# PSU.net
KiCad netlist of a schematic drawn in Altium Designer
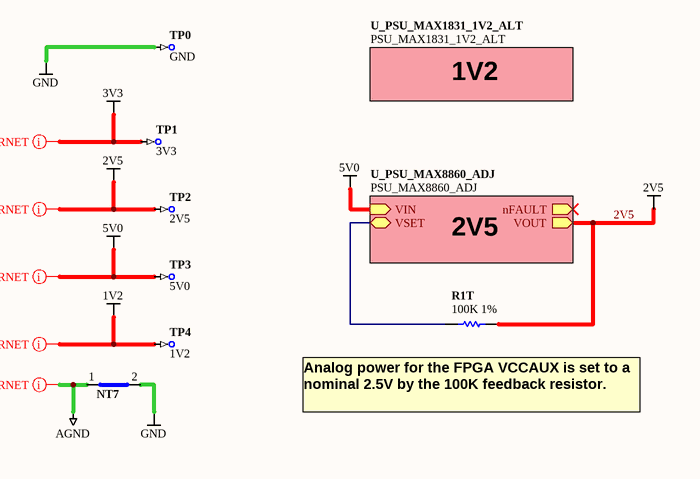
[diagram p0: PSU.SCHDOC]

(export (version "E")
  (design (tool "Eeschema 10.0.6"))
  (components
    (comp (ref "NT7")
      (value "Net Tie SMT2")
      (footprint "NETTIE-SMT2-8X8")
      (description "Net-Tie, Surface Mount, 2 x 0.4mm x 0.2mm SMT Pads - For 0.2mm Track")
      (libsource (lib "AltiumDesignLibrary") (part "NETTIE-SMT2"))
    )
    (comp (ref "R1T")
      (value "100K 1%")
      (footprint "RESC1005-STAR")
      (description "Resistor, 100K 1% 0402 (1005)")
      (fields (field (name "TOLERANCE") "1 %"))
      (libsource (lib "AltiumDesignLibrary") (part "RES"))
    )
    (comp (ref "TP0")
      (value "GND")
      (footprint "TestPin")
      (description "Test Point, PCB Mount with Silkscreen Box")
      (libsource (lib "AltiumDesignLibrary") (part "TestPin"))
    )
    (comp (ref "TP1")
      (value "3V3")
      (footprint "TestPin")
      (description "Test Point, PCB Mount with Silkscreen Box")
      (libsource (lib "AltiumDesignLibrary") (part "TestPin"))
    )
    (comp (ref "TP2")
      (value "2V5")
      (footprint "TestPin")
      (description "Test Point, PCB Mount with Silkscreen Box")
      (libsource (lib "AltiumDesignLibrary") (part "TestPin"))
    )
    (comp (ref "TP3")
      (value "5V0")
      (footprint "TestPin")
      (description "Test Point, PCB Mount with Silkscreen Box")
      (libsource (lib "AltiumDesignLibrary") (part "TestPin"))
    )
    (comp (ref "TP4")
      (value "1V2")
      (footprint "TestPin")
      (description "Test Point, PCB Mount with Silkscreen Box")
      (libsource (lib "AltiumDesignLibrary") (part "TestPin"))
    )
  )
  (nets
    (net (code "1") (name "/VSET") (class "Default")
      (node (ref "R1T") (pin "1") (pinfunction "1_1") (pintype "passive"))
    )
    (net (code "3") (name "1V2") (class "Default")
      (node (ref "TP4") (pin "1") (pinfunction "1_1") (pintype "input"))
    )
    (net (code "4") (name "2V5") (class "Default")
      (node (ref "R1T") (pin "2") (pinfunction "2_2") (pintype "passive"))
      (node (ref "TP2") (pin "1") (pinfunction "1_1") (pintype "input"))
    )
    (net (code "5") (name "3V3") (class "Default")
      (node (ref "TP1") (pin "1") (pinfunction "1_1") (pintype "input"))
    )
    (net (code "6") (name "5V0") (class "Default")
      (node (ref "TP3") (pin "1") (pinfunction "1_1") (pintype "input"))
    )
    (net (code "7") (name "AGND") (class "Default")
      (node (ref "NT7") (pin "1") (pinfunction "Net1_1") (pintype "passive"))
    )
    (net (code "8") (name "GND") (class "Default")
      (node (ref "NT7") (pin "2") (pinfunction "Net2_2") (pintype "passive"))
      (node (ref "TP0") (pin "1") (pinfunction "1_1") (pintype "input"))
    )
  )
)
